# p.net
KiCad netlist of a schematic drawn in EAGLE
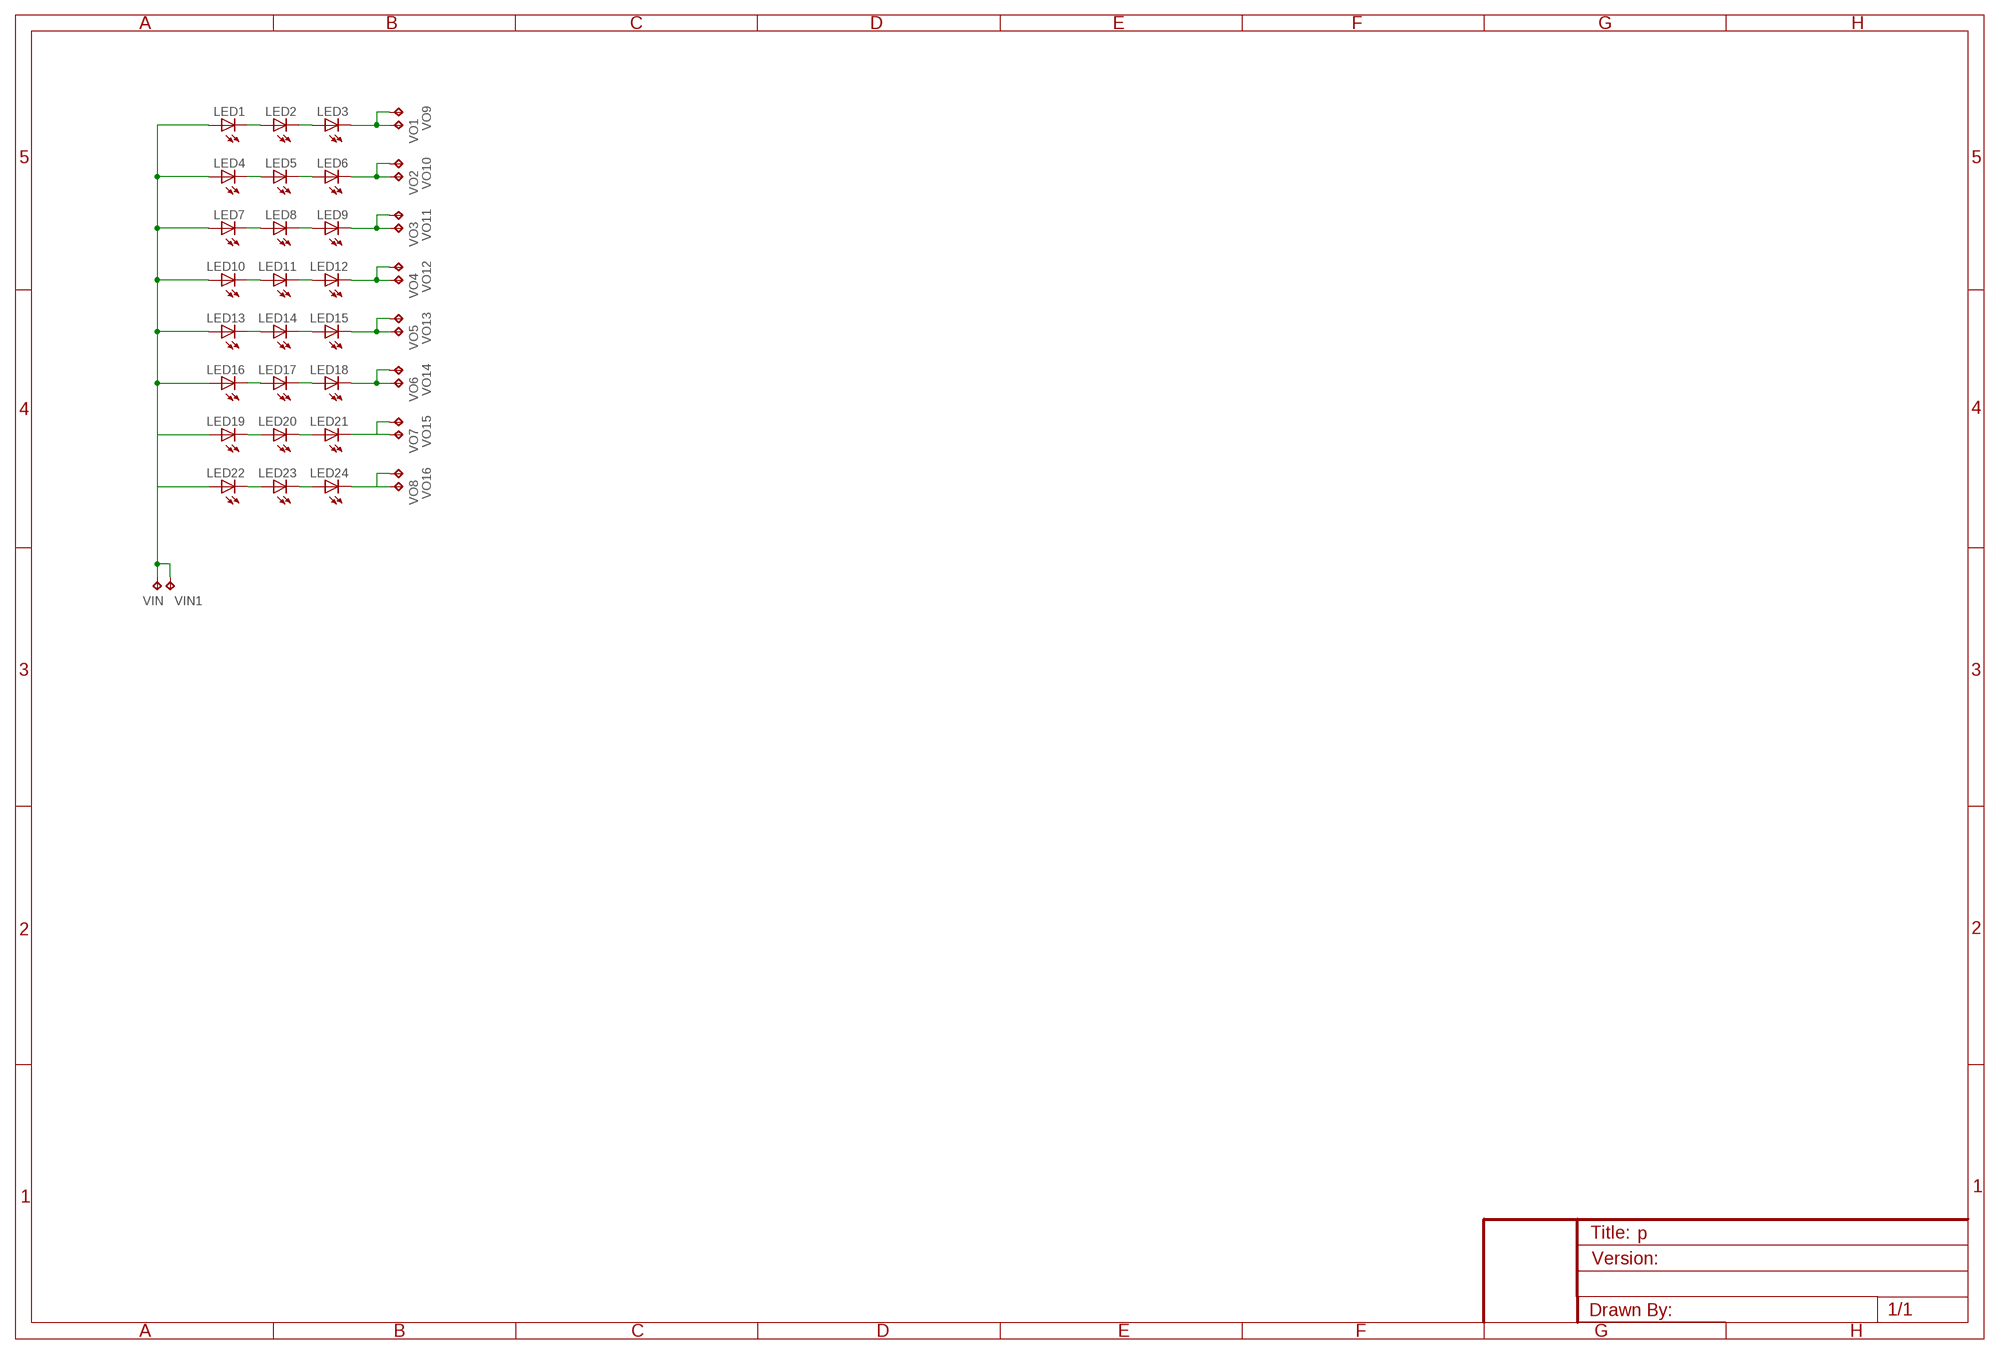
[diagram p0: schematic, sheet 1]

(export (version "E")
  (design (tool "Eeschema 10.0.6"))
  (components
    (comp (ref "LED1")
      (value "LED0805")
      (footprint "eagle-import:LED_0805")
      (libsource (lib "eagle-import") (part "LED0805"))
    )
    (comp (ref "LED2")
      (value "LED0805")
      (footprint "eagle-import:LED_0805")
      (libsource (lib "eagle-import") (part "LED0805"))
    )
    (comp (ref "LED3")
      (value "LED0805")
      (footprint "eagle-import:LED_0805")
      (libsource (lib "eagle-import") (part "LED0805"))
    )
    (comp (ref "LED4")
      (value "LED0805")
      (footprint "eagle-import:LED_0805")
      (libsource (lib "eagle-import") (part "LED0805"))
    )
    (comp (ref "LED5")
      (value "LED0805")
      (footprint "eagle-import:LED_0805")
      (libsource (lib "eagle-import") (part "LED0805"))
    )
    (comp (ref "LED6")
      (value "LED0805")
      (footprint "eagle-import:LED_0805")
      (libsource (lib "eagle-import") (part "LED0805"))
    )
    (comp (ref "LED7")
      (value "LED0805")
      (footprint "eagle-import:LED_0805")
      (libsource (lib "eagle-import") (part "LED0805"))
    )
    (comp (ref "LED8")
      (value "LED0805")
      (footprint "eagle-import:LED_0805")
      (libsource (lib "eagle-import") (part "LED0805"))
    )
    (comp (ref "LED9")
      (value "LED0805")
      (footprint "eagle-import:LED_0805")
      (libsource (lib "eagle-import") (part "LED0805"))
    )
    (comp (ref "LED10")
      (value "LED0805")
      (footprint "eagle-import:LED_0805")
      (libsource (lib "eagle-import") (part "LED0805"))
    )
    (comp (ref "LED11")
      (value "LED0805")
      (footprint "eagle-import:LED_0805")
      (libsource (lib "eagle-import") (part "LED0805"))
    )
    (comp (ref "LED12")
      (value "LED0805")
      (footprint "eagle-import:LED_0805")
      (libsource (lib "eagle-import") (part "LED0805"))
    )
    (comp (ref "LED13")
      (value "LED0805")
      (footprint "eagle-import:LED_0805")
      (libsource (lib "eagle-import") (part "LED0805"))
    )
    (comp (ref "LED14")
      (value "LED0805")
      (footprint "eagle-import:LED_0805")
      (libsource (lib "eagle-import") (part "LED0805"))
    )
    (comp (ref "LED15")
      (value "LED0805")
      (footprint "eagle-import:LED_0805")
      (libsource (lib "eagle-import") (part "LED0805"))
    )
    (comp (ref "LED16")
      (value "LED0805")
      (footprint "eagle-import:LED_0805")
      (libsource (lib "eagle-import") (part "LED0805"))
    )
    (comp (ref "LED17")
      (value "LED0805")
      (footprint "eagle-import:LED_0805")
      (libsource (lib "eagle-import") (part "LED0805"))
    )
    (comp (ref "LED18")
      (value "LED0805")
      (footprint "eagle-import:LED_0805")
      (libsource (lib "eagle-import") (part "LED0805"))
    )
    (comp (ref "LED19")
      (value "LED0805")
      (footprint "eagle-import:LED_0805")
      (libsource (lib "eagle-import") (part "LED0805"))
    )
    (comp (ref "LED20")
      (value "LED0805")
      (footprint "eagle-import:LED_0805")
      (libsource (lib "eagle-import") (part "LED0805"))
    )
    (comp (ref "LED21")
      (value "LED0805")
      (footprint "eagle-import:LED_0805")
      (libsource (lib "eagle-import") (part "LED0805"))
    )
    (comp (ref "LED22")
      (value "LED0805")
      (footprint "eagle-import:LED_0805")
      (libsource (lib "eagle-import") (part "LED0805"))
    )
    (comp (ref "LED23")
      (value "LED0805")
      (footprint "eagle-import:LED_0805")
      (libsource (lib "eagle-import") (part "LED0805"))
    )
    (comp (ref "LED24")
      (value "LED0805")
      (footprint "eagle-import:LED_0805")
      (libsource (lib "eagle-import") (part "LED0805"))
    )
    (comp (ref "VIN")
      (value "TEST_POINTPAD1-20")
      (footprint "eagle-import:P1-20")
      (libsource (lib "eagle-import") (part "TEST_POINTPAD1-20"))
    )
    (comp (ref "VIN1")
      (value "TEST_POINTPAD1-20")
      (footprint "eagle-import:P1-20")
      (libsource (lib "eagle-import") (part "TEST_POINTPAD1-20"))
    )
    (comp (ref "VO1")
      (value "TEST_POINTPAD1-20")
      (footprint "eagle-import:P1-20")
      (libsource (lib "eagle-import") (part "TEST_POINTPAD1-20"))
    )
    (comp (ref "VO2")
      (value "TEST_POINTPAD1-20")
      (footprint "eagle-import:P1-20")
      (libsource (lib "eagle-import") (part "TEST_POINTPAD1-20"))
    )
    (comp (ref "VO3")
      (value "TEST_POINTPAD1-20")
      (footprint "eagle-import:P1-20")
      (libsource (lib "eagle-import") (part "TEST_POINTPAD1-20"))
    )
    (comp (ref "VO4")
      (value "TEST_POINTPAD1-20")
      (footprint "eagle-import:P1-20")
      (libsource (lib "eagle-import") (part "TEST_POINTPAD1-20"))
    )
    (comp (ref "VO5")
      (value "TEST_POINTPAD1-20")
      (footprint "eagle-import:P1-20")
      (libsource (lib "eagle-import") (part "TEST_POINTPAD1-20"))
    )
    (comp (ref "VO6")
      (value "TEST_POINTPAD1-20")
      (footprint "eagle-import:P1-20")
      (libsource (lib "eagle-import") (part "TEST_POINTPAD1-20"))
    )
    (comp (ref "VO7")
      (value "TEST_POINTPAD1-20")
      (footprint "eagle-import:P1-20")
      (libsource (lib "eagle-import") (part "TEST_POINTPAD1-20"))
    )
    (comp (ref "VO8")
      (value "TEST_POINTPAD1-20")
      (footprint "eagle-import:P1-20")
      (libsource (lib "eagle-import") (part "TEST_POINTPAD1-20"))
    )
    (comp (ref "VO9")
      (value "TEST_POINTPAD1-20")
      (footprint "eagle-import:P1-20")
      (libsource (lib "eagle-import") (part "TEST_POINTPAD1-20"))
    )
    (comp (ref "VO10")
      (value "TEST_POINTPAD1-20")
      (footprint "eagle-import:P1-20")
      (libsource (lib "eagle-import") (part "TEST_POINTPAD1-20"))
    )
    (comp (ref "VO11")
      (value "TEST_POINTPAD1-20")
      (footprint "eagle-import:P1-20")
      (libsource (lib "eagle-import") (part "TEST_POINTPAD1-20"))
    )
    (comp (ref "VO12")
      (value "TEST_POINTPAD1-20")
      (footprint "eagle-import:P1-20")
      (libsource (lib "eagle-import") (part "TEST_POINTPAD1-20"))
    )
    (comp (ref "VO13")
      (value "TEST_POINTPAD1-20")
      (footprint "eagle-import:P1-20")
      (libsource (lib "eagle-import") (part "TEST_POINTPAD1-20"))
    )
    (comp (ref "VO14")
      (value "TEST_POINTPAD1-20")
      (footprint "eagle-import:P1-20")
      (libsource (lib "eagle-import") (part "TEST_POINTPAD1-20"))
    )
    (comp (ref "VO15")
      (value "TEST_POINTPAD1-20")
      (footprint "eagle-import:P1-20")
      (libsource (lib "eagle-import") (part "TEST_POINTPAD1-20"))
    )
    (comp (ref "VO16")
      (value "TEST_POINTPAD1-20")
      (footprint "eagle-import:P1-20")
      (libsource (lib "eagle-import") (part "TEST_POINTPAD1-20"))
    )
  )
  (nets
    (net (code "1") (name "Net-(LED1-PadA)") (class "Default")
      (node (ref "LED1") (pin "A") (pinfunction "A_A") (pintype "passive"))
      (node (ref "LED10") (pin "A") (pinfunction "A_A") (pintype "passive"))
      (node (ref "LED13") (pin "A") (pinfunction "A_A") (pintype "passive"))
      (node (ref "LED16") (pin "A") (pinfunction "A_A") (pintype "passive"))
      (node (ref "LED19") (pin "A") (pinfunction "A_A") (pintype "passive"))
      (node (ref "LED22") (pin "A") (pinfunction "A_A") (pintype "passive"))
      (node (ref "LED4") (pin "A") (pinfunction "A_A") (pintype "passive"))
      (node (ref "LED7") (pin "A") (pinfunction "A_A") (pintype "passive"))
      (node (ref "VIN") (pin "TP") (pinfunction "TP_TP") (pintype "input"))
      (node (ref "VIN1") (pin "TP") (pinfunction "TP_TP") (pintype "input"))
    )
    (net (code "2") (name "Net-(LED1-PadC)") (class "Default")
      (node (ref "LED1") (pin "C") (pinfunction "C_C") (pintype "passive"))
      (node (ref "LED2") (pin "A") (pinfunction "A_A") (pintype "passive"))
    )
    (net (code "3") (name "Net-(LED2-PadC)") (class "Default")
      (node (ref "LED2") (pin "C") (pinfunction "C_C") (pintype "passive"))
      (node (ref "LED3") (pin "A") (pinfunction "A_A") (pintype "passive"))
    )
    (net (code "4") (name "Net-(LED3-PadC)") (class "Default")
      (node (ref "LED3") (pin "C") (pinfunction "C_C") (pintype "passive"))
      (node (ref "VO1") (pin "TP") (pinfunction "TP_TP") (pintype "input"))
      (node (ref "VO9") (pin "TP") (pinfunction "TP_TP") (pintype "input"))
    )
    (net (code "5") (name "Net-(LED4-PadC)") (class "Default")
      (node (ref "LED4") (pin "C") (pinfunction "C_C") (pintype "passive"))
      (node (ref "LED5") (pin "A") (pinfunction "A_A") (pintype "passive"))
    )
    (net (code "6") (name "Net-(LED5-PadC)") (class "Default")
      (node (ref "LED5") (pin "C") (pinfunction "C_C") (pintype "passive"))
      (node (ref "LED6") (pin "A") (pinfunction "A_A") (pintype "passive"))
    )
    (net (code "7") (name "Net-(LED6-PadC)") (class "Default")
      (node (ref "LED6") (pin "C") (pinfunction "C_C") (pintype "passive"))
      (node (ref "VO10") (pin "TP") (pinfunction "TP_TP") (pintype "input"))
      (node (ref "VO2") (pin "TP") (pinfunction "TP_TP") (pintype "input"))
    )
    (net (code "8") (name "Net-(LED7-PadC)") (class "Default")
      (node (ref "LED7") (pin "C") (pinfunction "C_C") (pintype "passive"))
      (node (ref "LED8") (pin "A") (pinfunction "A_A") (pintype "passive"))
    )
    (net (code "9") (name "Net-(LED8-PadC)") (class "Default")
      (node (ref "LED8") (pin "C") (pinfunction "C_C") (pintype "passive"))
      (node (ref "LED9") (pin "A") (pinfunction "A_A") (pintype "passive"))
    )
    (net (code "10") (name "Net-(LED9-PadC)") (class "Default")
      (node (ref "LED9") (pin "C") (pinfunction "C_C") (pintype "passive"))
      (node (ref "VO11") (pin "TP") (pinfunction "TP_TP") (pintype "input"))
      (node (ref "VO3") (pin "TP") (pinfunction "TP_TP") (pintype "input"))
    )
    (net (code "11") (name "Net-(LED10-PadC)") (class "Default")
      (node (ref "LED10") (pin "C") (pinfunction "C_C") (pintype "passive"))
      (node (ref "LED11") (pin "A") (pinfunction "A_A") (pintype "passive"))
    )
    (net (code "12") (name "Net-(LED11-PadC)") (class "Default")
      (node (ref "LED11") (pin "C") (pinfunction "C_C") (pintype "passive"))
      (node (ref "LED12") (pin "A") (pinfunction "A_A") (pintype "passive"))
    )
    (net (code "13") (name "Net-(LED12-PadC)") (class "Default")
      (node (ref "LED12") (pin "C") (pinfunction "C_C") (pintype "passive"))
      (node (ref "VO12") (pin "TP") (pinfunction "TP_TP") (pintype "input"))
      (node (ref "VO4") (pin "TP") (pinfunction "TP_TP") (pintype "input"))
    )
    (net (code "14") (name "Net-(LED13-PadC)") (class "Default")
      (node (ref "LED13") (pin "C") (pinfunction "C_C") (pintype "passive"))
      (node (ref "LED14") (pin "A") (pinfunction "A_A") (pintype "passive"))
    )
    (net (code "15") (name "Net-(LED14-PadC)") (class "Default")
      (node (ref "LED14") (pin "C") (pinfunction "C_C") (pintype "passive"))
      (node (ref "LED15") (pin "A") (pinfunction "A_A") (pintype "passive"))
    )
    (net (code "16") (name "Net-(LED15-PadC)") (class "Default")
      (node (ref "LED15") (pin "C") (pinfunction "C_C") (pintype "passive"))
      (node (ref "VO13") (pin "TP") (pinfunction "TP_TP") (pintype "input"))
      (node (ref "VO5") (pin "TP") (pinfunction "TP_TP") (pintype "input"))
    )
    (net (code "17") (name "Net-(LED16-PadC)") (class "Default")
      (node (ref "LED16") (pin "C") (pinfunction "C_C") (pintype "passive"))
      (node (ref "LED17") (pin "A") (pinfunction "A_A") (pintype "passive"))
    )
    (net (code "18") (name "Net-(LED17-PadC)") (class "Default")
      (node (ref "LED17") (pin "C") (pinfunction "C_C") (pintype "passive"))
      (node (ref "LED18") (pin "A") (pinfunction "A_A") (pintype "passive"))
    )
    (net (code "19") (name "Net-(LED18-PadC)") (class "Default")
      (node (ref "LED18") (pin "C") (pinfunction "C_C") (pintype "passive"))
      (node (ref "VO14") (pin "TP") (pinfunction "TP_TP") (pintype "input"))
      (node (ref "VO6") (pin "TP") (pinfunction "TP_TP") (pintype "input"))
    )
    (net (code "20") (name "Net-(LED19-PadC)") (class "Default")
      (node (ref "LED19") (pin "C") (pinfunction "C_C") (pintype "passive"))
      (node (ref "LED20") (pin "A") (pinfunction "A_A") (pintype "passive"))
    )
    (net (code "21") (name "Net-(LED20-PadC)") (class "Default")
      (node (ref "LED20") (pin "C") (pinfunction "C_C") (pintype "passive"))
      (node (ref "LED21") (pin "A") (pinfunction "A_A") (pintype "passive"))
    )
    (net (code "22") (name "Net-(LED21-PadC)") (class "Default")
      (node (ref "LED21") (pin "C") (pinfunction "C_C") (pintype "passive"))
      (node (ref "VO15") (pin "TP") (pinfunction "TP_TP") (pintype "input"))
      (node (ref "VO7") (pin "TP") (pinfunction "TP_TP") (pintype "input"))
    )
    (net (code "23") (name "Net-(LED22-PadC)") (class "Default")
      (node (ref "LED22") (pin "C") (pinfunction "C_C") (pintype "passive"))
      (node (ref "LED23") (pin "A") (pinfunction "A_A") (pintype "passive"))
    )
    (net (code "24") (name "Net-(LED23-PadC)") (class "Default")
      (node (ref "LED23") (pin "C") (pinfunction "C_C") (pintype "passive"))
      (node (ref "LED24") (pin "A") (pinfunction "A_A") (pintype "passive"))
    )
    (net (code "25") (name "Net-(LED24-PadC)") (class "Default")
      (node (ref "LED24") (pin "C") (pinfunction "C_C") (pintype "passive"))
      (node (ref "VO16") (pin "TP") (pinfunction "TP_TP") (pintype "input"))
      (node (ref "VO8") (pin "TP") (pinfunction "TP_TP") (pintype "input"))
    )
  )
)
